# SONAR.net
KiCad netlist of a schematic drawn in Altium Designer
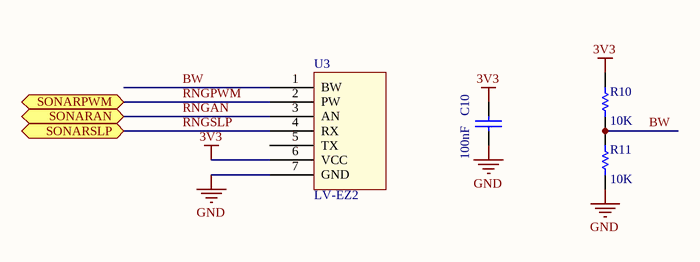
[diagram p0: SONAR.SchDoc]

(export (version "E")
  (design (tool "Eeschema 10.0.6"))
  (components
    (comp (ref "C10")
      (value "CAP0805-100NF")
      (footprint "RESC2012L")
      (description "CAP 0805 100nF")
      (fields (field (name "ALTIUM_UNNAMED_1") "100nF"))
      (libsource (lib "CapSMT") (part "CAP 0805 100nF"))
    )
    (comp (ref "R10")
      (value "10K")
      (footprint "RESC2012L")
      (description "Semiconductor Resistor")
      (fields (field (name "Comment") "RES0805-10K") (field (name "PUBLISHER") "Altium Limited"))
      (libsource (lib "Miscellaneous Devices") (part "Res Semi"))
    )
    (comp (ref "R11")
      (value "10K")
      (footprint "RESC2012L")
      (description "Semiconductor Resistor")
      (fields (field (name "Comment") "RES0805-10K") (field (name "PUBLISHER") "Altium Limited"))
      (libsource (lib "Miscellaneous Devices") (part "Res Semi"))
    )
    (comp (ref "U3")
      (value "LV-EZ2")
      (footprint "LV-EZ2")
      (description "Ultrasonic Sensor")
      (libsource (lib "Library") (part "LV-EZ2"))
    )
  )
  (nets
    (net (code "1") (name "/BW") (class "Default")
      (node (ref "R10") (pin "1") (pinfunction "1_1") (pintype "passive"))
      (node (ref "R11") (pin "2") (pinfunction "2_2") (pintype "passive"))
      (node (ref "U3") (pin "1") (pinfunction "BW_1") (pintype "passive"))
    )
    (net (code "2") (name "/RNGAN") (class "Default")
      (node (ref "U3") (pin "3") (pinfunction "AN_3") (pintype "passive"))
    )
    (net (code "3") (name "/RNGPWM") (class "Default")
      (node (ref "U3") (pin "2") (pinfunction "PW_2") (pintype "passive"))
    )
    (net (code "4") (name "/RNGSLP") (class "Default")
      (node (ref "U3") (pin "4") (pinfunction "RX_4") (pintype "passive"))
    )
    (net (code "5") (name "3V3") (class "Default")
      (node (ref "C10") (pin "1") (pintype "passive"))
      (node (ref "R10") (pin "2") (pinfunction "2_2") (pintype "passive"))
      (node (ref "U3") (pin "6") (pinfunction "VCC_6") (pintype "passive"))
    )
    (net (code "6") (name "GND") (class "Default")
      (node (ref "C10") (pin "2") (pintype "passive"))
      (node (ref "R11") (pin "1") (pinfunction "1_1") (pintype "passive"))
      (node (ref "U3") (pin "7") (pinfunction "GND_7") (pintype "passive"))
    )
    (net (code "7") (name "unconnected-(U3-TX-Pad5)") (class "Default")
      (node (ref "U3") (pin "5") (pinfunction "TX_5") (pintype "passive"))
    )
  )
)
